# Sheet1.net
KiCad netlist of a schematic drawn in Altium Designer
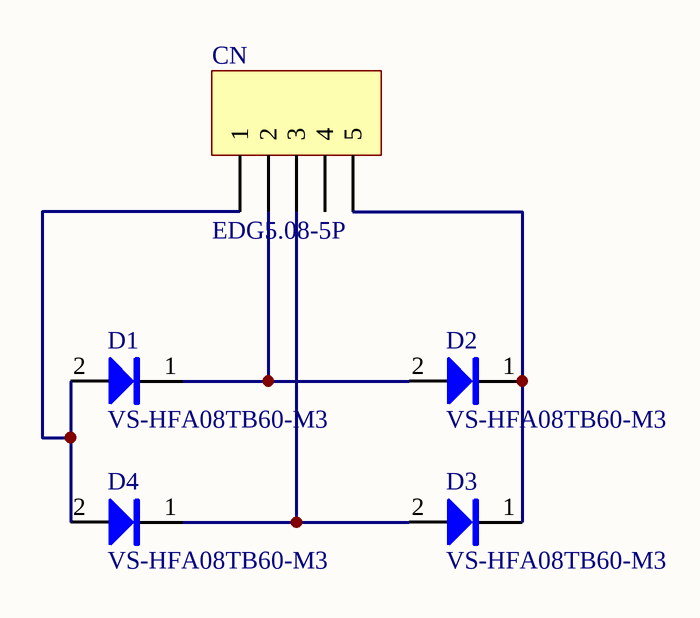
[diagram p0: Sheet1.SchDoc]

(export (version "E")
  (design (tool "Eeschema 10.0.6"))
  (components
    (comp (ref "CN")
      (value "EDG5.08-5P")
      (footprint "HX5.08-5L")
      (libsource (lib "Connectors") (part "EDG5.08-5P"))
    )
    (comp (ref "D1")
      (value "VS-HFA08TB60-M3")
      (footprint "TO220AC")
      (description "Ultrafast Soft Recovery Diado 8A 600V")
      (libsource (lib "二极管-整流桥") (part "VS-HFA08TB60-M3"))
    )
    (comp (ref "D2")
      (value "VS-HFA08TB60-M3")
      (footprint "TO220AC")
      (description "Ultrafast Soft Recovery Diado 8A 600V")
      (libsource (lib "二极管-整流桥") (part "VS-HFA08TB60-M3"))
    )
    (comp (ref "D3")
      (value "VS-HFA08TB60-M3")
      (footprint "TO220AC")
      (description "Ultrafast Soft Recovery Diado 8A 600V")
      (libsource (lib "二极管-整流桥") (part "VS-HFA08TB60-M3"))
    )
    (comp (ref "D4")
      (value "VS-HFA08TB60-M3")
      (footprint "TO220AC")
      (description "Ultrafast Soft Recovery Diado 8A 600V")
      (libsource (lib "二极管-整流桥") (part "VS-HFA08TB60-M3"))
    )
  )
  (nets
    (net (code "1") (name "Net-(D1-Anode)") (class "Default")
      (node (ref "CN") (pin "1") (pinfunction "1_1") (pintype "passive"))
      (node (ref "D1") (pin "2") (pinfunction "Anode_2") (pintype "passive"))
      (node (ref "D4") (pin "2") (pinfunction "Anode_2") (pintype "passive"))
    )
    (net (code "2") (name "Net-(D1-Cathode)") (class "Default")
      (node (ref "CN") (pin "2") (pinfunction "2_2") (pintype "passive"))
      (node (ref "D1") (pin "1") (pinfunction "Cathode_1") (pintype "passive"))
      (node (ref "D2") (pin "2") (pinfunction "Anode_2") (pintype "passive"))
    )
    (net (code "3") (name "Net-(D2-Cathode)") (class "Default")
      (node (ref "CN") (pin "5") (pinfunction "5_5") (pintype "passive"))
      (node (ref "D2") (pin "1") (pinfunction "Cathode_1") (pintype "passive"))
      (node (ref "D3") (pin "1") (pinfunction "Cathode_1") (pintype "passive"))
    )
    (net (code "4") (name "Net-(D3-Anode)") (class "Default")
      (node (ref "CN") (pin "3") (pinfunction "3_3") (pintype "passive"))
      (node (ref "D3") (pin "2") (pinfunction "Anode_2") (pintype "passive"))
      (node (ref "D4") (pin "1") (pinfunction "Cathode_1") (pintype "passive"))
    )
    (net (code "5") (name "unconnected-(CN-Pad4)") (class "Default")
      (node (ref "CN") (pin "4") (pinfunction "4_4") (pintype "passive"))
    )
  )
)
